# MP2565_dev_v1.net
KiCad netlist of a schematic drawn in EAGLE
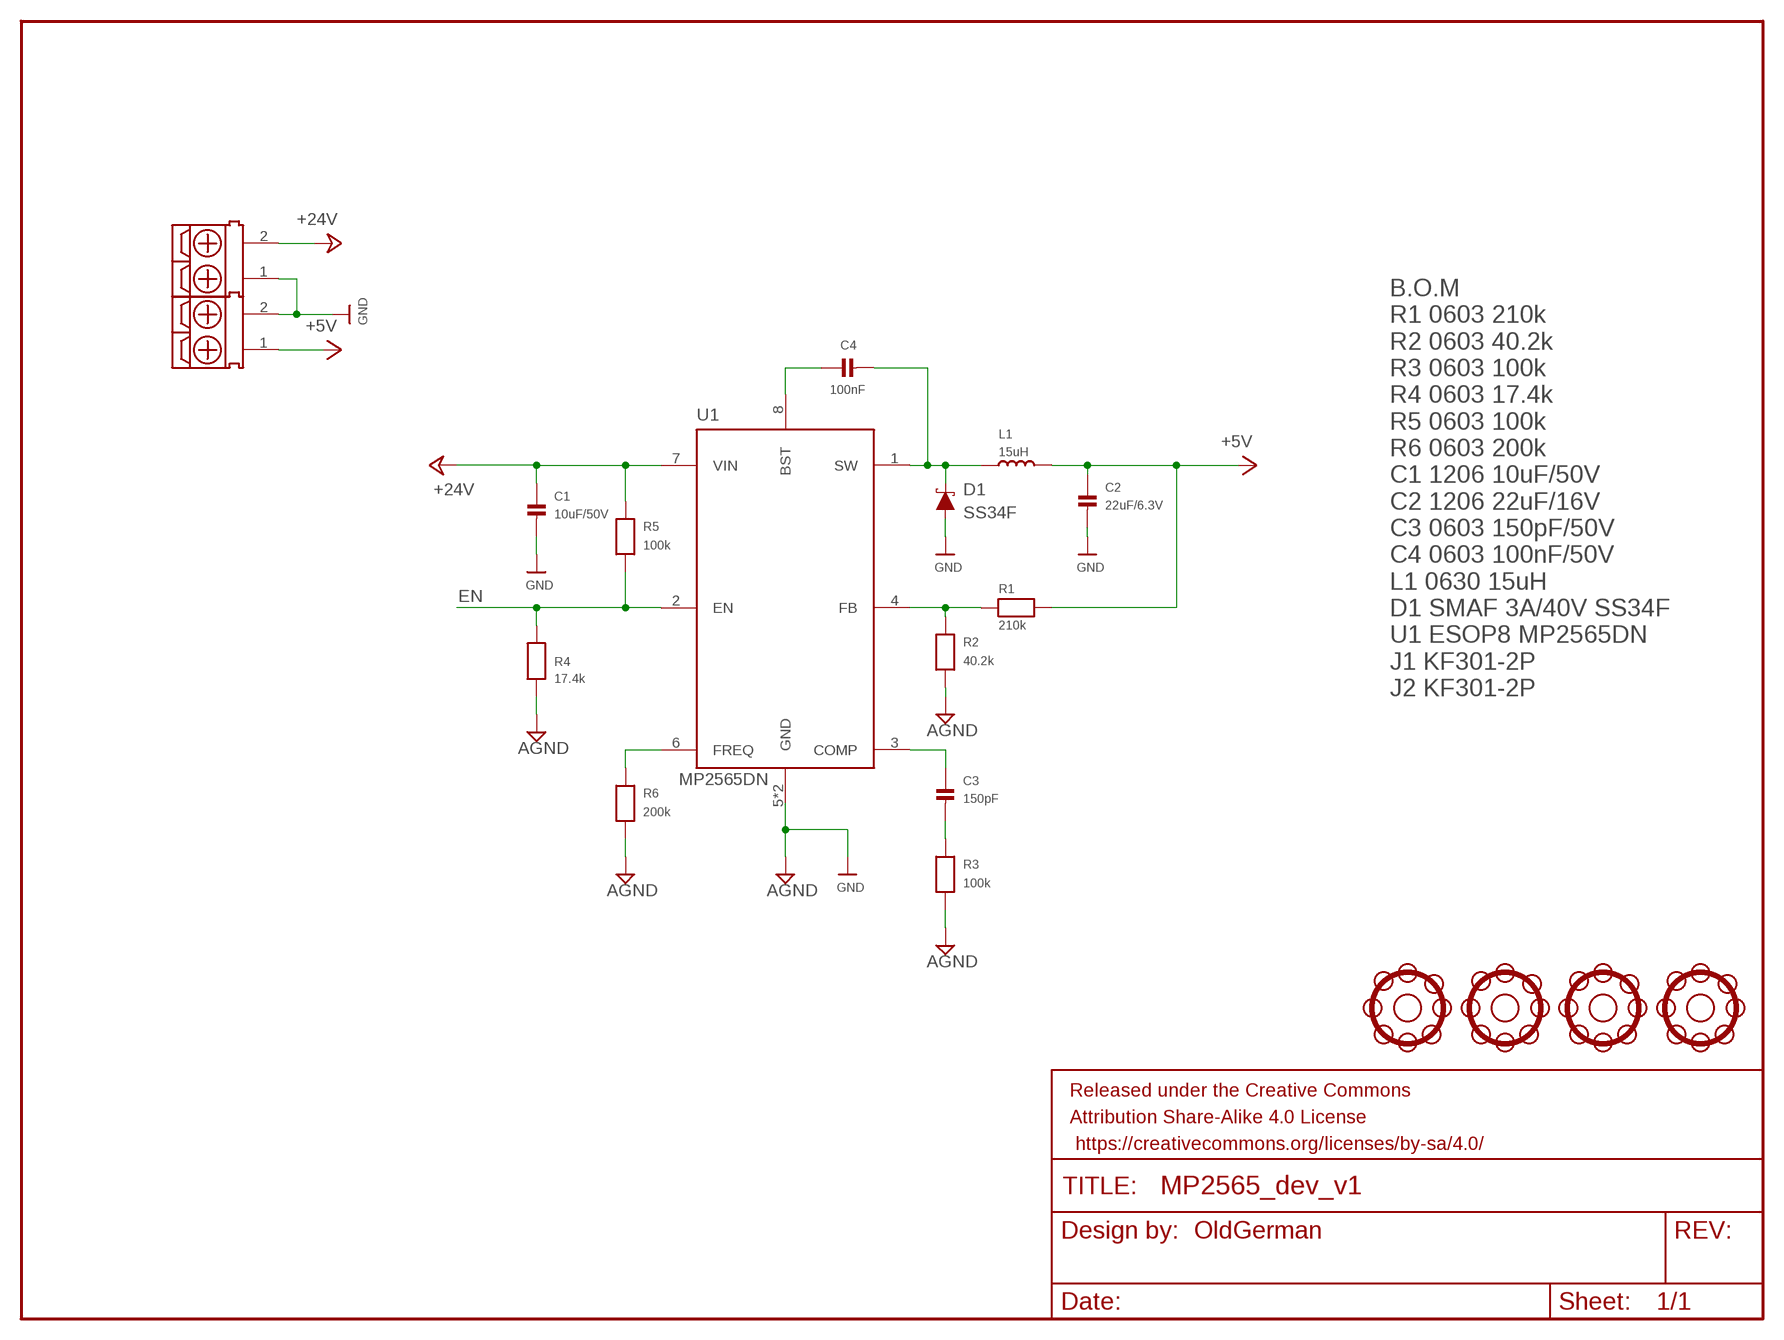
[diagram p0: schematic, sheet 1]

(export (version "E")
  (design (tool "Eeschema 10.0.6"))
  (components
    (comp (ref "C1")
      (value "10uF/50V")
      (footprint "eagle-import:1206")
      (libsource (lib "eagle-import") (part "CAP_CERAMIC1206"))
    )
    (comp (ref "C2")
      (value "22uF/6.3V")
      (footprint "eagle-import:1206")
      (libsource (lib "eagle-import") (part "CAP_CERAMIC1206"))
    )
    (comp (ref "C3")
      (value "150pF")
      (footprint "eagle-import:0603")
      (libsource (lib "eagle-import") (part "CAP_CERAMIC0603"))
    )
    (comp (ref "C4")
      (value "100nF")
      (footprint "eagle-import:0603")
      (libsource (lib "eagle-import") (part "CAP_CERAMIC0603"))
    )
    (comp (ref "D1")
      (value "SS34F")
      (footprint "eagle-import:SMAF")
      (libsource (lib "eagle-import") (part "SS34F"))
    )
    (comp (ref "FRAME1")
      (value "FRAME-LETTER")
      (footprint "eagle-import:CREATIVE_COMMONS")
      (libsource (lib "eagle-import") (part "FRAME-LETTER"))
    )
    (comp (ref "J1")
      (value "KF301_2P-5.0MM")
      (footprint "eagle-import:KF301__2P-5.0MM")
      (libsource (lib "eagle-import") (part "KF301_2P-5.0MM"))
    )
    (comp (ref "J2")
      (value "KF301_2P-5.0MM")
      (footprint "eagle-import:KF301__2P-5.0MM")
      (libsource (lib "eagle-import") (part "KF301_2P-5.0MM"))
    )
    (comp (ref "L1")
      (value "15uH")
      (footprint "eagle-import:L0630")
      (libsource (lib "eagle-import") (part "INDUCTOR'0630'"))
    )
    (comp (ref "R1")
      (value "210k")
      (footprint "eagle-import:0603")
      (libsource (lib "eagle-import") (part "RESISTOR0603"))
    )
    (comp (ref "R2")
      (value "40.2k")
      (footprint "eagle-import:0603")
      (libsource (lib "eagle-import") (part "RESISTOR0603"))
    )
    (comp (ref "R3")
      (value "100k")
      (footprint "eagle-import:0603")
      (libsource (lib "eagle-import") (part "RESISTOR0603"))
    )
    (comp (ref "R4")
      (value "17.4k")
      (footprint "eagle-import:0603")
      (libsource (lib "eagle-import") (part "RESISTOR0603"))
    )
    (comp (ref "R5")
      (value "100k")
      (footprint "eagle-import:0603")
      (libsource (lib "eagle-import") (part "RESISTOR0603"))
    )
    (comp (ref "R6")
      (value "200k")
      (footprint "eagle-import:0603")
      (libsource (lib "eagle-import") (part "RESISTOR0603"))
    )
    (comp (ref "U$13")
      (value "SUN_HOLE_M3")
      (footprint "eagle-import:SUN_HOLE_M3")
      (libsource (lib "eagle-import") (part "SUN_HOLE_M3"))
    )
    (comp (ref "U$14")
      (value "SUN_HOLE_M3")
      (footprint "eagle-import:SUN_HOLE_M3")
      (libsource (lib "eagle-import") (part "SUN_HOLE_M3"))
    )
    (comp (ref "U$15")
      (value "SUN_HOLE_M3")
      (footprint "eagle-import:SUN_HOLE_M3")
      (libsource (lib "eagle-import") (part "SUN_HOLE_M3"))
    )
    (comp (ref "U$16")
      (value "SUN_HOLE_M3")
      (footprint "eagle-import:SUN_HOLE_M3")
      (libsource (lib "eagle-import") (part "SUN_HOLE_M3"))
    )
    (comp (ref "U1")
      (value "MP2565DN")
      (footprint "eagle-import:ESOP8L-1.27-5X3.9MM")
      (libsource (lib "eagle-import") (part "MP2565DN"))
    )
  )
  (nets
    (net (code "1") (name "+5V") (class "Default")
      (node (ref "C2") (pin "1") (pinfunction "P$1_1") (pintype "passive"))
      (node (ref "J2") (pin "1") (pinfunction "P$1_1") (pintype "bidirectional"))
      (node (ref "L1") (pin "2") (pinfunction "2_2") (pintype "passive"))
      (node (ref "R1") (pin "2") (pinfunction "2_2") (pintype "passive"))
    )
    (net (code "2") (name "+24V") (class "Default")
      (node (ref "C1") (pin "1") (pinfunction "P$1_1") (pintype "passive"))
      (node (ref "J1") (pin "2") (pinfunction "P$2_2") (pintype "bidirectional"))
      (node (ref "R5") (pin "2") (pinfunction "2_2") (pintype "passive"))
      (node (ref "U1") (pin "7") (pinfunction "VIN_7") (pintype "bidirectional"))
    )
    (net (code "3") (name "/EN") (class "Default")
      (node (ref "R4") (pin "1") (pinfunction "1_1") (pintype "passive"))
      (node (ref "R5") (pin "1") (pinfunction "1_1") (pintype "passive"))
      (node (ref "U1") (pin "2") (pinfunction "EN_2") (pintype "bidirectional"))
    )
    (net (code "4") (name "AGND") (class "Default")
      (node (ref "C1") (pin "2") (pinfunction "P$2_2") (pintype "passive"))
      (node (ref "C2") (pin "2") (pinfunction "P$2_2") (pintype "passive"))
      (node (ref "D1") (pin "A") (pinfunction "A_A") (pintype "passive"))
      (node (ref "J1") (pin "1") (pinfunction "P$1_1") (pintype "bidirectional"))
      (node (ref "J2") (pin "2") (pinfunction "P$2_2") (pintype "bidirectional"))
      (node (ref "R2") (pin "1") (pinfunction "1_1") (pintype "passive"))
      (node (ref "R3") (pin "1") (pinfunction "1_1") (pintype "passive"))
      (node (ref "R4") (pin "2") (pinfunction "2_2") (pintype "passive"))
      (node (ref "R6") (pin "1") (pinfunction "1_1") (pintype "passive"))
      (node (ref "U1") (pin "5") (pinfunction "GND_5") (pintype "bidirectional"))
      (node (ref "U1") (pin "PAD") (pinfunction "GND_PAD") (pintype "bidirectional"))
    )
    (net (code "5") (name "Net-(C3-P$1)") (class "Default")
      (node (ref "C3") (pin "1") (pinfunction "P$1_1") (pintype "passive"))
      (node (ref "U1") (pin "3") (pinfunction "COMP_3") (pintype "bidirectional"))
    )
    (net (code "6") (name "Net-(C3-P$2)") (class "Default")
      (node (ref "C3") (pin "2") (pinfunction "P$2_2") (pintype "passive"))
      (node (ref "R3") (pin "2") (pinfunction "2_2") (pintype "passive"))
    )
    (net (code "7") (name "Net-(C4-P$1)") (class "Default")
      (node (ref "C4") (pin "1") (pinfunction "P$1_1") (pintype "passive"))
      (node (ref "U1") (pin "8") (pinfunction "BST_8") (pintype "bidirectional"))
    )
    (net (code "8") (name "Net-(C4-P$2)") (class "Default")
      (node (ref "C4") (pin "2") (pinfunction "P$2_2") (pintype "passive"))
      (node (ref "D1") (pin "C") (pinfunction "C_C") (pintype "passive"))
      (node (ref "L1") (pin "1") (pinfunction "1_1") (pintype "passive"))
      (node (ref "U1") (pin "1") (pinfunction "SW_1") (pintype "bidirectional"))
    )
    (net (code "9") (name "Net-(U1-FB)") (class "Default")
      (node (ref "R1") (pin "1") (pinfunction "1_1") (pintype "passive"))
      (node (ref "R2") (pin "2") (pinfunction "2_2") (pintype "passive"))
      (node (ref "U1") (pin "4") (pinfunction "FB_4") (pintype "bidirectional"))
    )
    (net (code "10") (name "Net-(U1-FREQ)") (class "Default")
      (node (ref "R6") (pin "2") (pinfunction "2_2") (pintype "passive"))
      (node (ref "U1") (pin "6") (pinfunction "FREQ_6") (pintype "bidirectional"))
    )
  )
)
